# SCH-5-ESC3.net
KiCad netlist of a schematic drawn in Altium Designer
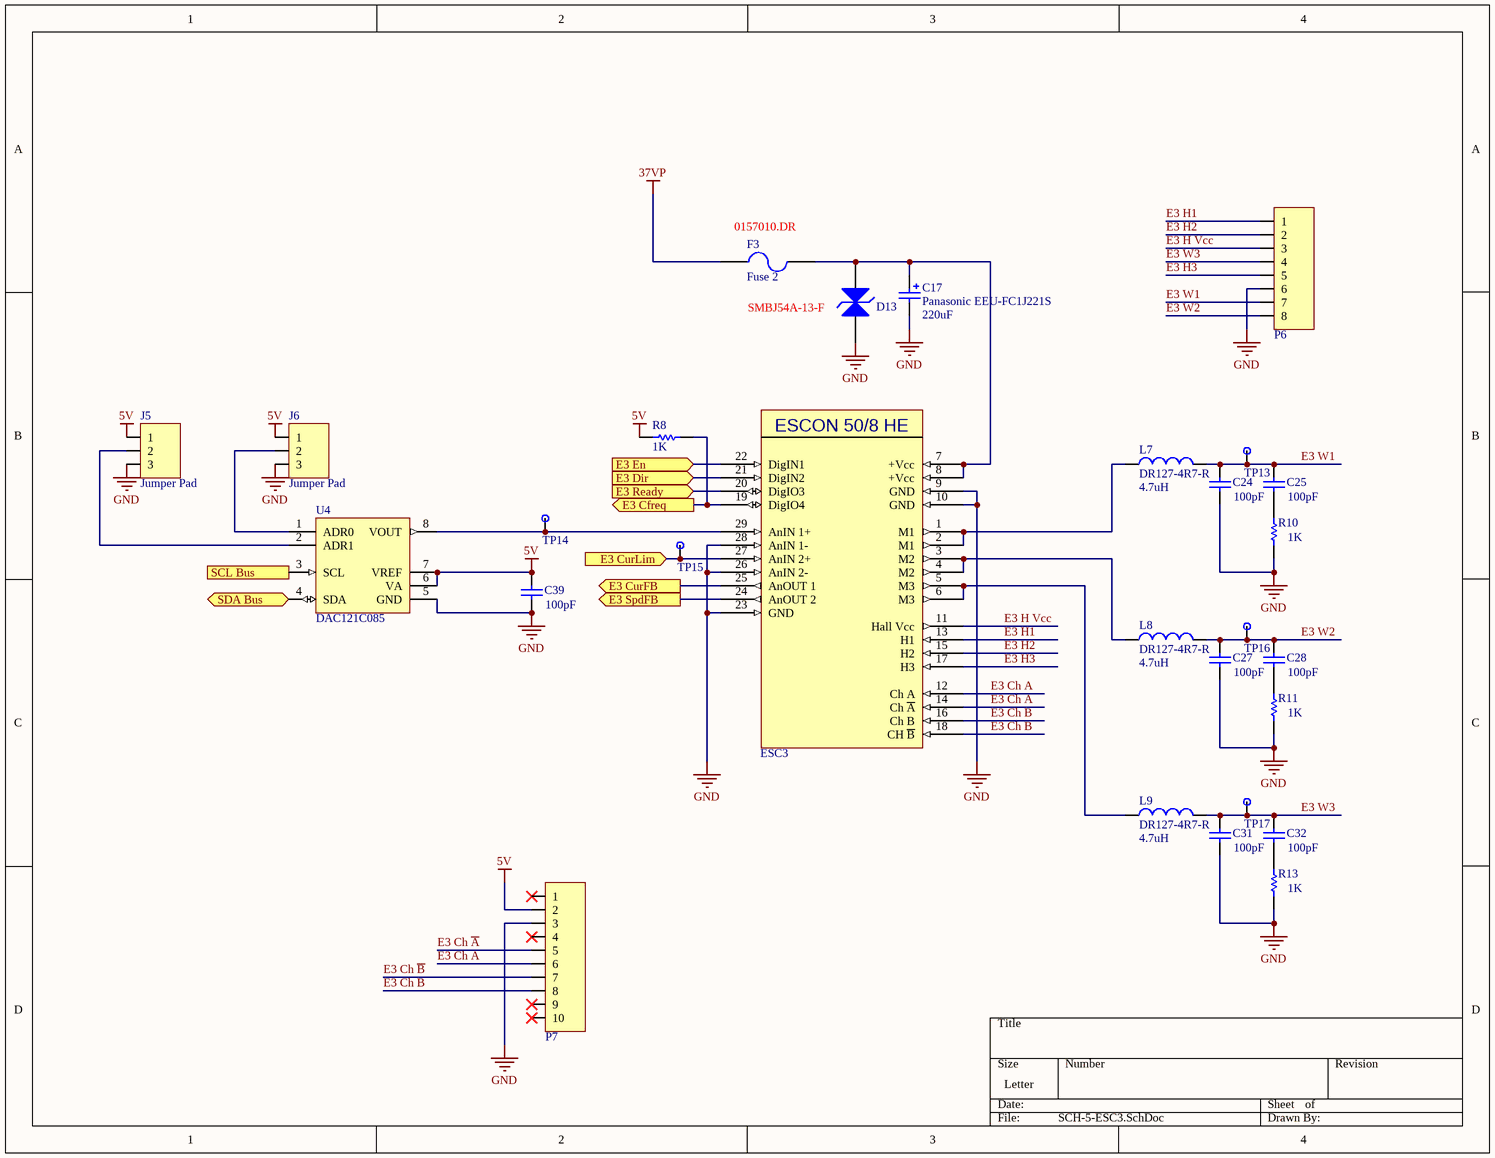
[diagram p0: SCH-5-ESC3.SchDoc]

(export (version "E")
  (design (tool "Eeschema 10.0.6"))
  (components
    (comp (ref "C17")
      (value "Panasonic EEU-FC1J221S")
      (footprint "Panasonic EEU-FC1J221S")
      (description "Polarized Capacitor (Radial)")
      (fields (field (name "ALTIUM_VALUE") "220uF"))
      (libsource (lib "RSX_Capacitors") (part "Panasonic EEU-FC1J221S"))
    )
    (comp (ref "C24")
      (value "100pF")
      (footprint "C1206")
      (description "Capacitor (Semiconductor SIM Model)")
      (fields (field (name "Comment") "Cap Semi") (field (name "PUBLISHER") "Altium Limited"))
      (libsource (lib "Miscellaneous Devices") (part "Cap Semi"))
    )
    (comp (ref "C25")
      (value "100pF")
      (footprint "C1206")
      (description "Capacitor (Semiconductor SIM Model)")
      (fields (field (name "Comment") "Cap Semi") (field (name "PUBLISHER") "Altium Limited"))
      (libsource (lib "Miscellaneous Devices") (part "Cap Semi"))
    )
    (comp (ref "C27")
      (value "100pF")
      (footprint "C1206")
      (description "Capacitor (Semiconductor SIM Model)")
      (fields (field (name "Comment") "Cap Semi") (field (name "PUBLISHER") "Altium Limited"))
      (libsource (lib "Miscellaneous Devices") (part "Cap Semi"))
    )
    (comp (ref "C28")
      (value "100pF")
      (footprint "C1206")
      (description "Capacitor (Semiconductor SIM Model)")
      (fields (field (name "Comment") "Cap Semi") (field (name "PUBLISHER") "Altium Limited"))
      (libsource (lib "Miscellaneous Devices") (part "Cap Semi"))
    )
    (comp (ref "C31")
      (value "100pF")
      (footprint "C1206")
      (description "Capacitor (Semiconductor SIM Model)")
      (fields (field (name "Comment") "Cap Semi") (field (name "PUBLISHER") "Altium Limited"))
      (libsource (lib "Miscellaneous Devices") (part "Cap Semi"))
    )
    (comp (ref "C32")
      (value "100pF")
      (footprint "C1206")
      (description "Capacitor (Semiconductor SIM Model)")
      (fields (field (name "Comment") "Cap Semi") (field (name "PUBLISHER") "Altium Limited"))
      (libsource (lib "Miscellaneous Devices") (part "Cap Semi"))
    )
    (comp (ref "C39")
      (value "100pF")
      (footprint "C1206")
      (description "Capacitor (Semiconductor SIM Model)")
      (fields (field (name "Comment") "Cap Semi") (field (name "PUBLISHER") "Altium Limited"))
      (libsource (lib "Miscellaneous Devices") (part "Cap Semi"))
    )
    (comp (ref "D13")
      (value "TVS_DIODE")
      (footprint "SMBJ54A-13-F")
      (description "TVS Diode")
      (fields (field (name "PUBLISHER") "Altium Limited"))
      (libsource (lib "RSX_Diodes") (part "TVS_DIODE"))
    )
    (comp (ref "ESC3")
      (value "ESCON 50/8 HE")
      (footprint "ESCON 50/8 HE")
      (description "ESCON Module 50/8 HE Servocontroller")
      (libsource (lib "RSX_Modules") (part "ESCON 50/8 HE"))
    )
    (comp (ref "F3")
      (value "Fuse 2")
      (footprint "0157010.DR")
      (description "Fuse")
      (fields (field (name "PUBLISHER") "Altium Limited"))
      (libsource (lib "RSX_Miscellaneous") (part "Fuse 2"))
    )
    (comp (ref "J5")
      (value "Jumper Pad")
      (footprint "3 Pad TH")
      (libsource (lib "RSX_Test_Points") (part "3 Pad Jump Sel"))
    )
    (comp (ref "J6")
      (value "Jumper Pad")
      (footprint "3 Pad TH")
      (libsource (lib "RSX_Test_Points") (part "3 Pad Jump Sel"))
    )
    (comp (ref "L7")
      (value "DR127-4R7-R")
      (footprint "DR127-4R7-R")
      (description "4.7µH Shielded Wirewound Inductor 8.25A 9.17mOhm Nonstandard")
      (fields (field (name "ALTIUM_VALUE") "4.7uH") (field (name "PUBLISHER") "Altium Limited"))
      (libsource (lib "RSX_Inductors") (part "DR127-4R7-R"))
    )
    (comp (ref "L8")
      (value "DR127-4R7-R")
      (footprint "DR127-4R7-R")
      (description "4.7µH Shielded Wirewound Inductor 8.25A 9.17mOhm Nonstandard")
      (fields (field (name "ALTIUM_VALUE") "4.7uH") (field (name "PUBLISHER") "Altium Limited"))
      (libsource (lib "RSX_Inductors") (part "DR127-4R7-R"))
    )
    (comp (ref "L9")
      (value "DR127-4R7-R")
      (footprint "DR127-4R7-R")
      (description "4.7µH Shielded Wirewound Inductor 8.25A 9.17mOhm Nonstandard")
      (fields (field (name "ALTIUM_VALUE") "4.7uH") (field (name "PUBLISHER") "Altium Limited"))
      (libsource (lib "RSX_Inductors") (part "DR127-4R7-R"))
    )
    (comp (ref "P6")
      (value "Mini-Fit Jr 8 Pos")
      (footprint "Molex Mini-Fit Jr 0039281083")
      (libsource (lib "RSX_Connectors") (part "Molex Mini-Fit Jr 8pos Vert"))
    )
    (comp (ref "P7")
      (value "Header_10_Pos_Ribbon Male")
      (footprint "3M_2510-6002UB")
      (description "3M_2510-6002UB")
      (libsource (lib "RSX_Connectors") (part "Header_10_Pos_Ribbon Male"))
    )
    (comp (ref "R8")
      (value "1K")
      (footprint "RESC1608X06N_0603")
      (description "Resistor")
      (fields (field (name "Comment") "Res1") (field (name "PUBLISHER") "Altium Limited"))
      (libsource (lib "RSX_Resistors") (part "Res1"))
    )
    (comp (ref "R10")
      (value "1K")
      (footprint "RESC1608X06N_0603")
      (description "Resistor")
      (fields (field (name "Comment") "Res1") (field (name "PUBLISHER") "Altium Limited"))
      (libsource (lib "RSX_Resistors") (part "Res1"))
    )
    (comp (ref "R11")
      (value "1K")
      (footprint "RESC1608X06N_0603")
      (description "Resistor")
      (fields (field (name "Comment") "Res1") (field (name "PUBLISHER") "Altium Limited"))
      (libsource (lib "RSX_Resistors") (part "Res1"))
    )
    (comp (ref "R13")
      (value "1K")
      (footprint "RESC1608X06N_0603")
      (description "Resistor")
      (fields (field (name "Comment") "Res1") (field (name "PUBLISHER") "Altium Limited"))
      (libsource (lib "RSX_Resistors") (part "Res1"))
    )
    (comp (ref "TP13")
      (value "TestPt")
      (footprint "50_MIL_PAD")
      (libsource (lib "RSX_Test_Points") (part "TestPt"))
    )
    (comp (ref "TP14")
      (value "TestPt")
      (footprint "50_MIL_PAD")
      (libsource (lib "RSX_Test_Points") (part "TestPt"))
    )
    (comp (ref "TP15")
      (value "TestPt")
      (footprint "50_MIL_PAD")
      (libsource (lib "RSX_Test_Points") (part "TestPt"))
    )
    (comp (ref "TP16")
      (value "TestPt")
      (footprint "50_MIL_PAD")
      (libsource (lib "RSX_Test_Points") (part "TestPt"))
    )
    (comp (ref "TP17")
      (value "TestPt")
      (footprint "50_MIL_PAD")
      (libsource (lib "RSX_Test_Points") (part "TestPt"))
    )
    (comp (ref "U4")
      (value "DAC121C085")
      (footprint "MUA08A_L")
      (fields (field (name "MANUFACTURER") "National Semiconductor"))
      (libsource (lib "RSX_Schematics") (part "DAC121C085"))
    )
  )
  (nets
    (net (code "1") (name "/E3 Cfreq") (class "Default")
      (node (ref "ESC3") (pin "19") (pinfunction "DigIO4_19") (pintype "bidirectional"))
      (node (ref "R8") (pin "1") (pinfunction "1_1") (pintype "passive"))
    )
    (net (code "2") (name "/E3 Ch A") (class "Default")
      (node (ref "ESC3") (pin "12") (pinfunction "Ch_A_12") (pintype "input"))
      (node (ref "P7") (pin "6") (pinfunction "6_6") (pintype "passive"))
    )
    (net (code "3") (name "/E3 Ch B") (class "Default")
      (node (ref "ESC3") (pin "16") (pinfunction "Ch_B_16") (pintype "input"))
      (node (ref "P7") (pin "8") (pinfunction "8_8") (pintype "passive"))
    )
    (net (code "4") (name "/E3 Ch ~{A}") (class "Default")
      (node (ref "ESC3") (pin "14") (pinfunction "Ch_~{A}_14") (pintype "input"))
      (node (ref "P7") (pin "5") (pinfunction "5_5") (pintype "passive"))
    )
    (net (code "5") (name "/E3 Ch ~{B}") (class "Default")
      (node (ref "ESC3") (pin "18") (pinfunction "CH_~{B}_18") (pintype "input"))
      (node (ref "P7") (pin "7") (pinfunction "7_7") (pintype "passive"))
    )
    (net (code "6") (name "/E3 CurFB") (class "Default")
      (node (ref "ESC3") (pin "25") (pinfunction "AnOUT_1_25") (pintype "output"))
    )
    (net (code "7") (name "/E3 CurLim") (class "Default")
      (node (ref "ESC3") (pin "27") (pinfunction "AnIN_2+_27") (pintype "input"))
      (node (ref "TP15") (pin "1") (pinfunction "1_1") (pintype "passive"))
    )
    (net (code "8") (name "/E3 Dir") (class "Default")
      (node (ref "ESC3") (pin "21") (pinfunction "DigIN2_21") (pintype "input"))
    )
    (net (code "9") (name "/E3 En") (class "Default")
      (node (ref "ESC3") (pin "22") (pinfunction "DigIN1_22") (pintype "input"))
    )
    (net (code "10") (name "/E3 H Vcc") (class "Default")
      (node (ref "ESC3") (pin "11") (pinfunction "Hall_Vcc_11") (pintype "output"))
      (node (ref "P6") (pin "3") (pinfunction "3_3") (pintype "passive"))
    )
    (net (code "11") (name "/E3 H1") (class "Default")
      (node (ref "ESC3") (pin "13") (pinfunction "H1_13") (pintype "input"))
      (node (ref "P6") (pin "1") (pinfunction "1_1") (pintype "passive"))
    )
    (net (code "12") (name "/E3 H2") (class "Default")
      (node (ref "ESC3") (pin "15") (pinfunction "H2_15") (pintype "input"))
      (node (ref "P6") (pin "2") (pinfunction "2_2") (pintype "passive"))
    )
    (net (code "13") (name "/E3 H3") (class "Default")
      (node (ref "ESC3") (pin "17") (pinfunction "H3_17") (pintype "input"))
      (node (ref "P6") (pin "5") (pinfunction "5_5") (pintype "passive"))
    )
    (net (code "14") (name "/E3 Ready") (class "Default")
      (node (ref "ESC3") (pin "20") (pinfunction "DigIO3_20") (pintype "bidirectional"))
    )
    (net (code "15") (name "/E3 SpdFB") (class "Default")
      (node (ref "ESC3") (pin "24") (pinfunction "AnOUT_2_24") (pintype "output"))
    )
    (net (code "16") (name "/E3 W1") (class "Default")
      (node (ref "C24") (pin "2") (pinfunction "2_2") (pintype "passive"))
      (node (ref "C25") (pin "2") (pinfunction "2_2") (pintype "passive"))
      (node (ref "L7") (pin "2") (pinfunction "2_2") (pintype "passive"))
      (node (ref "P6") (pin "7") (pinfunction "7_7") (pintype "passive"))
      (node (ref "TP13") (pin "1") (pinfunction "1_1") (pintype "passive"))
    )
    (net (code "17") (name "/E3 W2") (class "Default")
      (node (ref "C27") (pin "2") (pinfunction "2_2") (pintype "passive"))
      (node (ref "C28") (pin "2") (pinfunction "2_2") (pintype "passive"))
      (node (ref "L8") (pin "2") (pinfunction "2_2") (pintype "passive"))
      (node (ref "P6") (pin "8") (pinfunction "8_8") (pintype "passive"))
      (node (ref "TP16") (pin "1") (pinfunction "1_1") (pintype "passive"))
    )
    (net (code "18") (name "/E3 W3") (class "Default")
      (node (ref "C31") (pin "2") (pinfunction "2_2") (pintype "passive"))
      (node (ref "C32") (pin "2") (pinfunction "2_2") (pintype "passive"))
      (node (ref "L9") (pin "2") (pinfunction "2_2") (pintype "passive"))
      (node (ref "P6") (pin "4") (pinfunction "4_4") (pintype "passive"))
      (node (ref "TP17") (pin "1") (pinfunction "1_1") (pintype "passive"))
    )
    (net (code "19") (name "/SCL Bus") (class "Default")
      (node (ref "U4") (pin "3") (pinfunction "SCL_3") (pintype "input"))
    )
    (net (code "20") (name "/SDA Bus") (class "Default")
      (node (ref "U4") (pin "4") (pinfunction "SDA_4") (pintype "bidirectional"))
    )
    (net (code "21") (name "5V") (class "Default")
      (node (ref "C39") (pin "2") (pinfunction "2_2") (pintype "passive"))
      (node (ref "J5") (pin "1") (pinfunction "1_1") (pintype "passive"))
      (node (ref "J6") (pin "1") (pinfunction "1_1") (pintype "passive"))
      (node (ref "P7") (pin "2") (pinfunction "2_2") (pintype "passive"))
      (node (ref "R8") (pin "2") (pinfunction "2_2") (pintype "passive"))
      (node (ref "U4") (pin "6") (pinfunction "VA_6") (pintype "power_in"))
      (node (ref "U4") (pin "7") (pinfunction "VREF_7") (pintype "power_in"))
    )
    (net (code "22") (name "37VP") (class "Default")
      (node (ref "F3") (pin "1") (pinfunction "1_1") (pintype "passive"))
    )
    (net (code "23") (name "GND") (class "Default")
      (node (ref "C17") (pin "2") (pinfunction "2_2") (pintype "passive"))
      (node (ref "C24") (pin "1") (pinfunction "1_1") (pintype "passive"))
      (node (ref "C27") (pin "1") (pinfunction "1_1") (pintype "passive"))
      (node (ref "C31") (pin "1") (pinfunction "1_1") (pintype "passive"))
      (node (ref "C39") (pin "1") (pinfunction "1_1") (pintype "passive"))
      (node (ref "D13") (pin "1") (pinfunction "A_1") (pintype "passive"))
      (node (ref "ESC3") (pin "10") (pinfunction "GND_10") (pintype "input"))
      (node (ref "ESC3") (pin "23") (pinfunction "GND_23") (pintype "input"))
      (node (ref "ESC3") (pin "26") (pinfunction "AnIN_2-_26") (pintype "input"))
      (node (ref "ESC3") (pin "28") (pinfunction "AnIN_1-_28") (pintype "input"))
      (node (ref "ESC3") (pin "9") (pinfunction "GND_9") (pintype "input"))
      (node (ref "J5") (pin "3") (pinfunction "3_3") (pintype "passive"))
      (node (ref "J6") (pin "3") (pinfunction "3_3") (pintype "passive"))
      (node (ref "P6") (pin "6") (pinfunction "6_6") (pintype "passive"))
      (node (ref "P7") (pin "3") (pinfunction "3_3") (pintype "passive"))
      (node (ref "R10") (pin "1") (pinfunction "1_1") (pintype "passive"))
      (node (ref "R11") (pin "1") (pinfunction "1_1") (pintype "passive"))
      (node (ref "R13") (pin "1") (pinfunction "1_1") (pintype "passive"))
      (node (ref "U4") (pin "5") (pinfunction "GND_5") (pintype "power_in"))
    )
    (net (code "24") (name "Net-(C25-Pad1)") (class "Default")
      (node (ref "C25") (pin "1") (pinfunction "1_1") (pintype "passive"))
      (node (ref "R10") (pin "2") (pinfunction "2_2") (pintype "passive"))
    )
    (net (code "25") (name "Net-(C28-Pad1)") (class "Default")
      (node (ref "C28") (pin "1") (pinfunction "1_1") (pintype "passive"))
      (node (ref "R11") (pin "2") (pinfunction "2_2") (pintype "passive"))
    )
    (net (code "26") (name "Net-(C32-Pad1)") (class "Default")
      (node (ref "C32") (pin "1") (pinfunction "1_1") (pintype "passive"))
      (node (ref "R13") (pin "2") (pinfunction "2_2") (pintype "passive"))
    )
    (net (code "27") (name "Net-(D13-K)") (class "Default")
      (node (ref "C17") (pin "1") (pinfunction "1_1") (pintype "passive"))
      (node (ref "D13") (pin "2") (pinfunction "K_2") (pintype "passive"))
      (node (ref "ESC3") (pin "7") (pinfunction "+Vcc_7") (pintype "input"))
      (node (ref "ESC3") (pin "8") (pinfunction "+Vcc_8") (pintype "input"))
      (node (ref "F3") (pin "2") (pinfunction "2_2") (pintype "passive"))
    )
    (net (code "28") (name "Net-(ESC3-AnIN_1+)") (class "Default")
      (node (ref "ESC3") (pin "29") (pinfunction "AnIN_1+_29") (pintype "input"))
      (node (ref "TP14") (pin "1") (pinfunction "1_1") (pintype "passive"))
      (node (ref "U4") (pin "8") (pinfunction "VOUT_8") (pintype "output"))
    )
    (net (code "29") (name "Net-(ESC3-M1-Pad1)") (class "Default")
      (node (ref "ESC3") (pin "1") (pinfunction "M1_1") (pintype "output"))
      (node (ref "ESC3") (pin "2") (pinfunction "M1_2") (pintype "output"))
      (node (ref "L7") (pin "1") (pinfunction "1_1") (pintype "passive"))
    )
    (net (code "30") (name "Net-(ESC3-M2-Pad3)") (class "Default")
      (node (ref "ESC3") (pin "3") (pinfunction "M2_3") (pintype "output"))
      (node (ref "ESC3") (pin "4") (pinfunction "M2_4") (pintype "output"))
      (node (ref "L8") (pin "1") (pinfunction "1_1") (pintype "passive"))
    )
    (net (code "31") (name "Net-(ESC3-M3-Pad5)") (class "Default")
      (node (ref "ESC3") (pin "5") (pinfunction "M3_5") (pintype "output"))
      (node (ref "ESC3") (pin "6") (pinfunction "M3_6") (pintype "output"))
      (node (ref "L9") (pin "1") (pinfunction "1_1") (pintype "passive"))
    )
    (net (code "32") (name "Net-(U4-ADR0)") (class "Default")
      (node (ref "J6") (pin "2") (pinfunction "2_2") (pintype "passive"))
      (node (ref "U4") (pin "1") (pinfunction "ADR0_1") (pintype "tri_state"))
    )
    (net (code "33") (name "Net-(U4-ADR1)") (class "Default")
      (node (ref "J5") (pin "2") (pinfunction "2_2") (pintype "passive"))
      (node (ref "U4") (pin "2") (pinfunction "ADR1_2") (pintype "tri_state"))
    )
    (net (code "34") (name "unconnected-(P7-Pad1)") (class "Default")
      (node (ref "P7") (pin "1") (pinfunction "1_1") (pintype "passive+no_connect"))
    )
    (net (code "35") (name "unconnected-(P7-Pad4)") (class "Default")
      (node (ref "P7") (pin "4") (pinfunction "4_4") (pintype "passive+no_connect"))
    )
    (net (code "36") (name "unconnected-(P7-Pad9)") (class "Default")
      (node (ref "P7") (pin "9") (pinfunction "9_9") (pintype "passive+no_connect"))
    )
    (net (code "37") (name "unconnected-(P7-Pad10)") (class "Default")
      (node (ref "P7") (pin "10") (pinfunction "10_10") (pintype "passive+no_connect"))
    )
  )
)
